# ACS_5_3.net
KiCad netlist of a schematic drawn in EAGLE
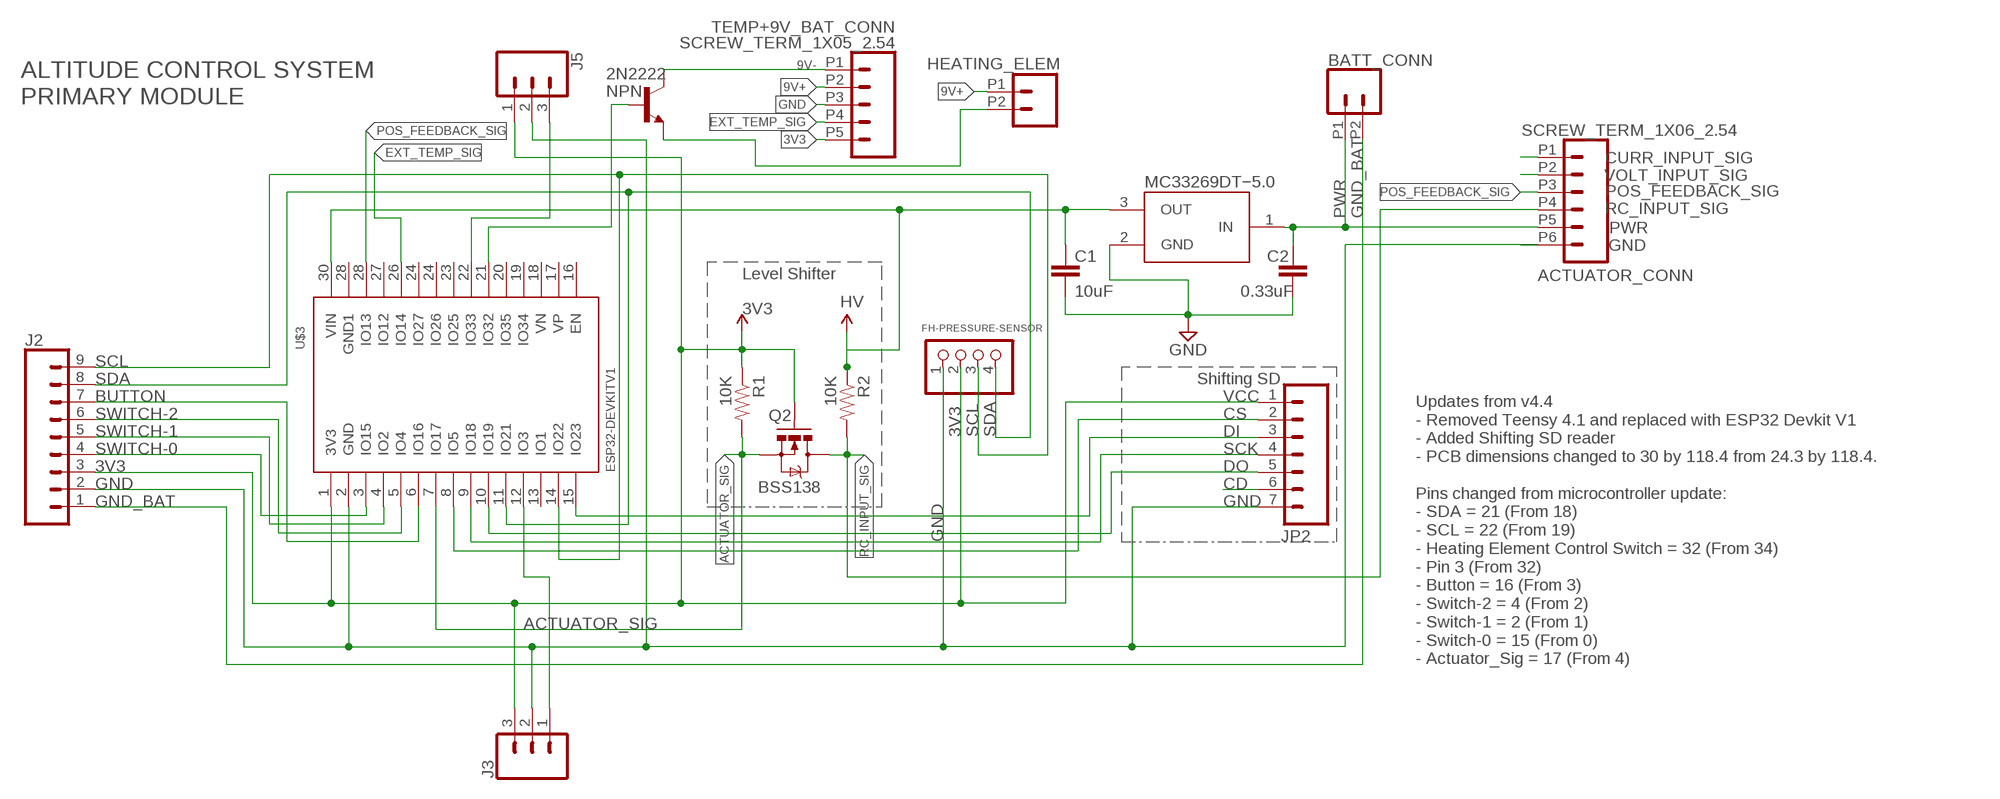
[diagram p0: schematic, sheet 1]

(export (version "E")
  (design (tool "Eeschema 10.0.6"))
  (components
    (comp (ref "2N2222")
      (value "NPN")
      (footprint "eagle-import:SOT95P237X112-3N")
      (libsource (lib "eagle-import") (part "NPNSOT23_"))
    )
    (comp (ref "ACTUATOR_CONN")
      (value "SCREW_TERM_1X06_2.54")
      (footprint "eagle-import:1X06_2.54_SCREWTERM")
      (libsource (lib "eagle-import") (part "SCREW_TERM_1X06_2.54"))
    )
    (comp (ref "BATT_CONN")
      (value "CONN_022.54MM_SCREWTERM")
      (footprint "eagle-import:1X02_2.54_SCREWTERM")
      (libsource (lib "eagle-import") (part "CONN_022.54MM_SCREWTERM"))
    )
    (comp (ref "C1")
      (value "10uF")
      (footprint "eagle-import:CAPC1608X85")
      (libsource (lib "eagle-import") (part "CCHIP-0603(1608-METRIC)_"))
    )
    (comp (ref "C2")
      (value "0.33uF")
      (footprint "eagle-import:CAPC1608X85")
      (libsource (lib "eagle-import") (part "CCHIP-0603(1608-METRIC)_"))
    )
    (comp (ref "FH-PRESSURE-SENSOR")
      (value "PINHD-1X4")
      (footprint "eagle-import:1X04")
      (libsource (lib "eagle-import") (part "PINHD-1X4"))
    )
    (comp (ref "HEATING_ELEM")
      (value "CONN_022.54MM_SCREWTERM")
      (footprint "eagle-import:1X02_2.54_SCREWTERM")
      (libsource (lib "eagle-import") (part "CONN_022.54MM_SCREWTERM"))
    )
    (comp (ref "J2")
      (value "CONN_09")
      (footprint "eagle-import:1X09")
      (libsource (lib "eagle-import") (part "CONN_09"))
    )
    (comp (ref "J3")
      (value "CONN_03")
      (footprint "eagle-import:1X03")
      (libsource (lib "eagle-import") (part "CONN_03"))
    )
    (comp (ref "J5")
      (value "CONN_03")
      (footprint "eagle-import:1X03")
      (libsource (lib "eagle-import") (part "CONN_03"))
    )
    (comp (ref "JP2")
      (value "M07")
      (footprint "eagle-import:1X07")
      (libsource (lib "eagle-import") (part "M07"))
    )
    (comp (ref "Q2")
      (value "BSS138")
      (footprint "eagle-import:SOT23-3")
      (libsource (lib "eagle-import") (part "MOSFET-NCHANNELSMD"))
    )
    (comp (ref "R1")
      (value "10K")
      (footprint "eagle-import:0603-RES")
      (libsource (lib "eagle-import") (part "RESISTOR0603-RES"))
    )
    (comp (ref "R2")
      (value "10K")
      (footprint "eagle-import:0603-RES")
      (libsource (lib "eagle-import") (part "RESISTOR0603-RES"))
    )
    (comp (ref "TEMP+9V_BAT_CONN")
      (value "SCREW_TERM_1X05_2.54")
      (footprint "eagle-import:1X05_2.54_SCREWTERM")
      (libsource (lib "eagle-import") (part "SCREW_TERM_1X05_2.54"))
    )
    (comp (ref "U$3")
      (value "ESP32DEVKITV1")
      (footprint "eagle-import:ESP32-DEVKITV1")
      (libsource (lib "eagle-import") (part "ESP32DEVKITV1"))
    )
    (comp (ref "U1")
      (value "MC78M05BDTRKG")
      (footprint "eagle-import:MC78M05BDTRKG")
      (fields
        (field (name "MANUFACTURER") "ON Semiconductor")
        (field (name "MPN") "IC REG LINEAR 5V 500MA DPAK")
        (field (name "CREATED_BY") "PCBLayout.com")
      )
      (libsource (lib "eagle-import") (part "MC78M05BDTRKG"))
    )
  )
  (nets
    (net (code "1") (name "/9V-") (class "Default")
      (node (ref "2N2222") (pin "3") (pinfunction "C_3") (pintype "passive"))
      (node (ref "TEMP+9V_BAT_CONN") (pin "P1") (pinfunction "1_P1") (pintype "passive"))
    )
    (net (code "2") (name "/BUTTON") (class "Default")
      (node (ref "J2") (pin "7") (pinfunction "7_7") (pintype "passive"))
      (node (ref "U$3") (pin "6") (pinfunction "IO16_6") (pintype "bidirectional"))
    )
    (net (code "3") (name "/CURR_INPUT_SIG") (class "Default")
      (node (ref "ACTUATOR_CONN") (pin "P1") (pinfunction "1_P1") (pintype "passive"))
    )
    (net (code "4") (name "/GND_BAT") (class "Default")
      (node (ref "BATT_CONN") (pin "P2") (pinfunction "2_P2") (pintype "passive"))
      (node (ref "J2") (pin "1") (pinfunction "1_1") (pintype "passive"))
    )
    (net (code "5") (name "/PWR") (class "Default")
      (node (ref "ACTUATOR_CONN") (pin "P5") (pinfunction "5_P5") (pintype "passive"))
      (node (ref "BATT_CONN") (pin "P1") (pinfunction "1_P1") (pintype "passive"))
      (node (ref "C2") (pin "1") (pinfunction "1_1") (pintype "passive"))
      (node (ref "U1") (pin "1") (pinfunction "IN_1") (pintype "input"))
    )
    (net (code "6") (name "/SCL") (class "Default")
      (node (ref "FH-PRESSURE-SENSOR") (pin "3") (pinfunction "3_3") (pintype "passive"))
      (node (ref "J2") (pin "9") (pinfunction "9_9") (pintype "passive"))
      (node (ref "U$3") (pin "14") (pinfunction "IO22_14") (pintype "bidirectional"))
    )
    (net (code "7") (name "/SDA") (class "Default")
      (node (ref "FH-PRESSURE-SENSOR") (pin "4") (pinfunction "4_4") (pintype "passive"))
      (node (ref "J2") (pin "8") (pinfunction "8_8") (pintype "passive"))
      (node (ref "U$3") (pin "11") (pinfunction "IO21_11") (pintype "bidirectional"))
    )
    (net (code "8") (name "/SWITCH-0") (class "Default")
      (node (ref "J2") (pin "4") (pinfunction "4_4") (pintype "passive"))
      (node (ref "U$3") (pin "3") (pinfunction "IO15_3") (pintype "bidirectional"))
    )
    (net (code "9") (name "/SWITCH-1") (class "Default")
      (node (ref "J2") (pin "5") (pinfunction "5_5") (pintype "passive"))
      (node (ref "U$3") (pin "4") (pinfunction "IO2_4") (pintype "bidirectional"))
    )
    (net (code "10") (name "/SWITCH-2") (class "Default")
      (node (ref "J2") (pin "6") (pinfunction "6_6") (pintype "passive"))
      (node (ref "U$3") (pin "5") (pinfunction "IO4_5") (pintype "bidirectional"))
    )
    (net (code "11") (name "/VOLT_INPUT_SIG") (class "Default")
      (node (ref "ACTUATOR_CONN") (pin "P2") (pinfunction "2_P2") (pintype "passive"))
    )
    (net (code "12") (name "3V3") (class "Default")
      (node (ref "FH-PRESSURE-SENSOR") (pin "2") (pinfunction "2_2") (pintype "passive"))
      (node (ref "J2") (pin "3") (pinfunction "3_3") (pintype "passive"))
      (node (ref "J3") (pin "3") (pinfunction "3_3") (pintype "passive"))
      (node (ref "J5") (pin "1") (pinfunction "1_1") (pintype "passive"))
      (node (ref "JP2") (pin "1") (pinfunction "1_1") (pintype "passive"))
      (node (ref "Q2") (pin "1") (pinfunction "G_1") (pintype "passive"))
      (node (ref "R1") (pin "1") (pinfunction "1_1") (pintype "passive"))
      (node (ref "TEMP+9V_BAT_CONN") (pin "P5") (pinfunction "5_P5") (pintype "passive"))
      (node (ref "U$3") (pin "1") (pinfunction "3V3_1") (pintype "bidirectional"))
    )
    (net (code "13") (name "9V+") (class "Default")
      (node (ref "HEATING_ELEM") (pin "P1") (pinfunction "1_P1") (pintype "passive"))
      (node (ref "TEMP+9V_BAT_CONN") (pin "P2") (pinfunction "2_P2") (pintype "passive"))
    )
    (net (code "14") (name "ACTUATOR_SIG") (class "Default")
      (node (ref "Q2") (pin "2") (pinfunction "S_2") (pintype "passive"))
      (node (ref "R1") (pin "2") (pinfunction "2_2") (pintype "passive"))
      (node (ref "U$3") (pin "7") (pinfunction "IO17_7") (pintype "bidirectional"))
    )
    (net (code "15") (name "EXT_TEMP_SIG") (class "Default")
      (node (ref "TEMP+9V_BAT_CONN") (pin "P4") (pinfunction "4_P4") (pintype "passive"))
      (node (ref "U$3") (pin "26") (pinfunction "IO14_26") (pintype "bidirectional"))
    )
    (net (code "16") (name "GND") (class "Default")
      (node (ref "ACTUATOR_CONN") (pin "P6") (pinfunction "6_P6") (pintype "passive"))
      (node (ref "C1") (pin "2") (pinfunction "2_2") (pintype "passive"))
      (node (ref "C2") (pin "2") (pinfunction "2_2") (pintype "passive"))
      (node (ref "FH-PRESSURE-SENSOR") (pin "1") (pinfunction "1_1") (pintype "passive"))
      (node (ref "J2") (pin "2") (pinfunction "2_2") (pintype "passive"))
      (node (ref "J3") (pin "2") (pinfunction "2_2") (pintype "passive"))
      (node (ref "J5") (pin "2") (pinfunction "2_2") (pintype "passive"))
      (node (ref "JP2") (pin "7") (pinfunction "7_7") (pintype "passive"))
      (node (ref "TEMP+9V_BAT_CONN") (pin "P3") (pinfunction "3_P3") (pintype "passive"))
      (node (ref "U$3") (pin "2") (pinfunction "GND_2") (pintype "bidirectional"))
      (node (ref "U1") (pin "2") (pinfunction "GND_2") (pintype "power_in"))
    )
    (net (code "17") (name "HV") (class "Default")
      (node (ref "C1") (pin "1") (pinfunction "1_1") (pintype "passive"))
      (node (ref "R2") (pin "1") (pinfunction "1_1") (pintype "passive"))
      (node (ref "U$3") (pin "30") (pinfunction "VIN_30") (pintype "bidirectional"))
      (node (ref "U1") (pin "3") (pinfunction "OUT_3") (pintype "output"))
    )
    (net (code "18") (name "Net-(2N2222-B)") (class "Default")
      (node (ref "2N2222") (pin "2") (pinfunction "B_2") (pintype "passive"))
      (node (ref "U$3") (pin "21") (pinfunction "IO32_21") (pintype "bidirectional"))
    )
    (net (code "19") (name "Net-(2N2222-E)") (class "Default")
      (node (ref "2N2222") (pin "1") (pinfunction "E_1") (pintype "passive"))
      (node (ref "HEATING_ELEM") (pin "P2") (pinfunction "2_P2") (pintype "passive"))
    )
    (net (code "20") (name "Net-(U$3-IO3)") (class "Default")
      (node (ref "J3") (pin "1") (pinfunction "1_1") (pintype "passive"))
      (node (ref "U$3") (pin "12") (pinfunction "IO3_12") (pintype "bidirectional"))
    )
    (net (code "21") (name "Net-(U$3-IO5)") (class "Default")
      (node (ref "JP2") (pin "2") (pinfunction "2_2") (pintype "passive"))
      (node (ref "U$3") (pin "8") (pinfunction "IO5_8") (pintype "bidirectional"))
    )
    (net (code "22") (name "Net-(U$3-IO18)") (class "Default")
      (node (ref "JP2") (pin "4") (pinfunction "4_4") (pintype "passive"))
      (node (ref "U$3") (pin "9") (pinfunction "IO18_9") (pintype "bidirectional"))
    )
    (net (code "23") (name "Net-(U$3-IO19)") (class "Default")
      (node (ref "JP2") (pin "5") (pinfunction "5_5") (pintype "passive"))
      (node (ref "U$3") (pin "10") (pinfunction "IO19_10") (pintype "bidirectional"))
    )
    (net (code "24") (name "Net-(U$3-IO23)") (class "Default")
      (node (ref "JP2") (pin "3") (pinfunction "3_3") (pintype "passive"))
      (node (ref "U$3") (pin "15") (pinfunction "IO23_15") (pintype "bidirectional"))
    )
    (net (code "25") (name "Net-(U$3-IO33)") (class "Default")
      (node (ref "J5") (pin "3") (pinfunction "3_3") (pintype "passive"))
      (node (ref "U$3") (pin "22") (pinfunction "IO33_22") (pintype "bidirectional"))
    )
    (net (code "26") (name "POS_FEEDBACK_SIG") (class "Default")
      (node (ref "ACTUATOR_CONN") (pin "P3") (pinfunction "3_P3") (pintype "passive"))
      (node (ref "U$3") (pin "28") (pinfunction "IO13_28") (pintype "bidirectional"))
    )
    (net (code "27") (name "RC_INPUT_SIG") (class "Default")
      (node (ref "ACTUATOR_CONN") (pin "P4") (pinfunction "4_P4") (pintype "passive"))
      (node (ref "Q2") (pin "3") (pinfunction "D_3") (pintype "passive"))
      (node (ref "R2") (pin "2") (pinfunction "2_2") (pintype "passive"))
    )
    (net (code "28") (name "unconnected-(JP2-Pad6)") (class "Default")
      (node (ref "JP2") (pin "6") (pinfunction "6_6") (pintype "passive"))
    )
    (net (code "29") (name "unconnected-(U$3-EN-Pad16)") (class "Default")
      (node (ref "U$3") (pin "16") (pinfunction "EN_16") (pintype "bidirectional"))
    )
    (net (code "30") (name "unconnected-(U$3-GND1-Pad28)") (class "Default")
      (node (ref "U$3") (pin "28") (pinfunction "GND1_28") (pintype "bidirectional"))
    )
    (net (code "31") (name "unconnected-(U$3-IO1-Pad13)") (class "Default")
      (node (ref "U$3") (pin "13") (pinfunction "IO1_13") (pintype "bidirectional"))
    )
    (net (code "32") (name "unconnected-(U$3-IO12-Pad27)") (class "Default")
      (node (ref "U$3") (pin "27") (pinfunction "IO12_27") (pintype "bidirectional"))
    )
    (net (code "33") (name "unconnected-(U$3-IO25-Pad23)") (class "Default")
      (node (ref "U$3") (pin "23") (pinfunction "IO25_23") (pintype "bidirectional"))
    )
    (net (code "34") (name "unconnected-(U$3-IO26-Pad24)") (class "Default")
      (node (ref "U$3") (pin "24") (pinfunction "IO26_24") (pintype "bidirectional"))
    )
    (net (code "35") (name "unconnected-(U$3-IO27-Pad24)") (class "Default")
      (node (ref "U$3") (pin "24") (pinfunction "IO27_24") (pintype "bidirectional"))
    )
    (net (code "36") (name "unconnected-(U$3-IO34-Pad19)") (class "Default")
      (node (ref "U$3") (pin "19") (pinfunction "IO34_19") (pintype "bidirectional"))
    )
    (net (code "37") (name "unconnected-(U$3-IO35-Pad20)") (class "Default")
      (node (ref "U$3") (pin "20") (pinfunction "IO35_20") (pintype "bidirectional"))
    )
    (net (code "38") (name "unconnected-(U$3-VN-Pad18)") (class "Default")
      (node (ref "U$3") (pin "18") (pinfunction "VN_18") (pintype "bidirectional"))
    )
    (net (code "39") (name "unconnected-(U$3-VP-Pad17)") (class "Default")
      (node (ref "U$3") (pin "17") (pinfunction "VP_17") (pintype "bidirectional"))
    )
  )
)
